# BIRDS-5_FM_-Z_Panel_Ver4.net
KiCad netlist of a schematic drawn in EAGLE
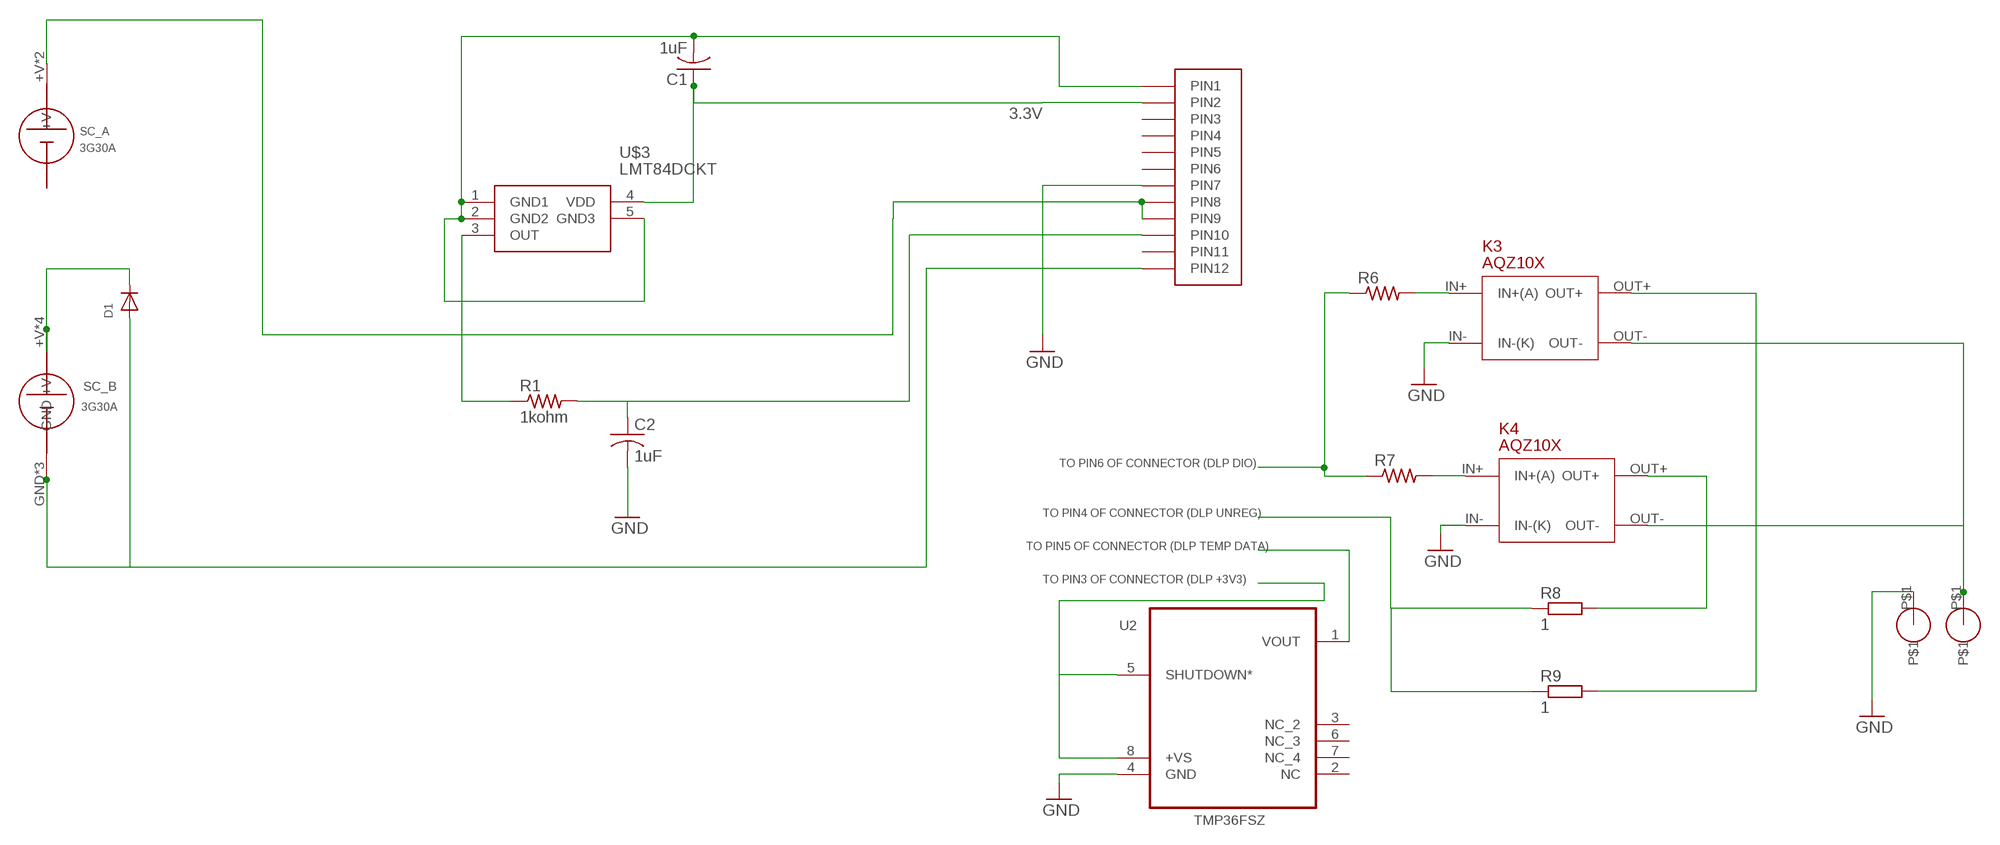
[diagram p0: schematic, sheet 1]

(export (version "E")
  (design (tool "Eeschema 10.0.6"))
  (components
    (comp (ref "C1")
      (value "1uF")
      (footprint "eagle-import:C0805")
      (libsource (lib "eagle-import") (part "C-USC0805"))
    )
    (comp (ref "C2")
      (value "1uF")
      (footprint "eagle-import:C0805")
      (libsource (lib "eagle-import") (part "C-USC0805"))
    )
    (comp (ref "D1")
      (value "DIODE_SOD-123FL")
      (footprint "eagle-import:SOD-123FL")
      (libsource (lib "eagle-import") (part "DIODE_SOD-123FL"))
    )
    (comp (ref "GND9")
      (value "NICR_HOLE")
      (footprint "eagle-import:NICR_HOLE")
      (libsource (lib "eagle-import") (part "NICR_HOLE"))
    )
    (comp (ref "HOLE1")
      (value "NICR_HOLE")
      (footprint "eagle-import:NICR_HOLE")
      (libsource (lib "eagle-import") (part "NICR_HOLE"))
    )
    (comp (ref "K3")
      (value "AQZ10X")
      (footprint "eagle-import:AQZ10X")
      (libsource (lib "eagle-import") (part "AQZ10X"))
    )
    (comp (ref "K4")
      (value "AQZ10X")
      (footprint "eagle-import:AQZ10X")
      (libsource (lib "eagle-import") (part "AQZ10X"))
    )
    (comp (ref "R1")
      (value "1kohm")
      (footprint "eagle-import:R0402")
      (libsource (lib "eagle-import") (part "R-US_R0402"))
    )
    (comp (ref "R6")
      (value "R-US_R0402")
      (footprint "eagle-import:R0402")
      (libsource (lib "eagle-import") (part "adafruit_ufl_R-US_R0402"))
    )
    (comp (ref "R7")
      (value "R-US_R0402")
      (footprint "eagle-import:R0402")
      (libsource (lib "eagle-import") (part "adafruit_ufl_R-US_R0402"))
    )
    (comp (ref "R8")
      (value "1")
      (footprint "eagle-import:R1218")
      (libsource (lib "eagle-import") (part "R-EU_R1218"))
    )
    (comp (ref "R9")
      (value "1")
      (footprint "eagle-import:R1218")
      (libsource (lib "eagle-import") (part "R-EU_R1218"))
    )
    (comp (ref "U$1")
      (value "HEADER12PIN")
      (footprint "eagle-import:HEADER12PIN")
      (libsource (lib "eagle-import") (part "HEADER12PIN"))
    )
    (comp (ref "U$3")
      (value "LMT84DCKT")
      (footprint "eagle-import:SOT65P210X110-5N")
      (fields (field (name "RS_PART_NUMBER") "8115860"))
      (libsource (lib "eagle-import") (part "LMT84DCKT"))
    )
    (comp (ref "U$4")
      (value "SC_A")
      (footprint "eagle-import:SC_A")
      (libsource (lib "eagle-import") (part "SC_A"))
    )
    (comp (ref "U$5")
      (value "SC_B")
      (footprint "eagle-import:SC_B")
      (libsource (lib "eagle-import") (part "SC_B"))
    )
    (comp (ref "U2")
      (value "TMP36FSZ")
      (footprint "eagle-import:SOIC_N")
      (libsource (lib "eagle-import") (part "TMP36FSZ"))
    )
  )
  (nets
    (net (code "1") (name "/3.3V") (class "Default")
      (node (ref "U2") (pin "5") (pinfunction "SHUTDOWN*_5") (pintype "passive"))
      (node (ref "U2") (pin "8") (pinfunction "+VS_8") (pintype "power_in"))
    )
    (net (code "2") (name "GND") (class "Default")
      (node (ref "C1") (pin "2") (pinfunction "2_2") (pintype "passive"))
      (node (ref "C2") (pin "2") (pinfunction "2_2") (pintype "passive"))
      (node (ref "D1") (pin "A") (pinfunction "A_A") (pintype "passive"))
      (node (ref "GND9") (pin "P$1") (pinfunction "P$1_P$1") (pintype "bidirectional"))
      (node (ref "K3") (pin "IN-") (pinfunction "IN-(K)_IN-") (pintype "bidirectional"))
      (node (ref "K4") (pin "IN-") (pinfunction "IN-(K)_IN-") (pintype "bidirectional"))
      (node (ref "U$1") (pin "P1") (pinfunction "PIN1_P1") (pintype "bidirectional"))
      (node (ref "U$1") (pin "P12") (pinfunction "PIN12_P12") (pintype "bidirectional"))
      (node (ref "U$1") (pin "P7") (pinfunction "PIN7_P7") (pintype "bidirectional"))
      (node (ref "U$3") (pin "1") (pinfunction "GND1_1") (pintype "power_in"))
      (node (ref "U$3") (pin "2") (pinfunction "GND2_2") (pintype "power_in"))
      (node (ref "U$3") (pin "5") (pinfunction "GND3_5") (pintype "power_in"))
      (node (ref "U$5") (pin "GND") (pinfunction "GND_GND") (pintype "bidirectional"))
      (node (ref "U$5") (pin "GND1") (pinfunction "GND_GND1") (pintype "bidirectional"))
      (node (ref "U$5") (pin "GND2") (pinfunction "GND_GND2") (pintype "bidirectional"))
      (node (ref "U2") (pin "4") (pinfunction "GND_4") (pintype "passive"))
    )
    (net (code "3") (name "Net-(D1-PadC)") (class "Default")
      (node (ref "D1") (pin "C") (pinfunction "C_C") (pintype "passive"))
      (node (ref "U$5") (pin "+V") (pinfunction "+V_+V") (pintype "bidirectional"))
      (node (ref "U$5") (pin "+V2") (pinfunction "+V_+V2") (pintype "bidirectional"))
      (node (ref "U$5") (pin "+V3") (pinfunction "+V_+V3") (pintype "bidirectional"))
      (node (ref "U$5") (pin "+V4") (pinfunction "+V_+V4") (pintype "bidirectional"))
    )
    (net (code "4") (name "Net-(HOLE1-PadP$1)") (class "Default")
      (node (ref "HOLE1") (pin "P$1") (pinfunction "P$1_P$1") (pintype "bidirectional"))
      (node (ref "K3") (pin "OUT-") (pinfunction "OUT-_OUT-") (pintype "bidirectional"))
      (node (ref "K4") (pin "OUT-") (pinfunction "OUT-_OUT-") (pintype "bidirectional"))
    )
    (net (code "5") (name "Net-(K3-IN+(A))") (class "Default")
      (node (ref "K3") (pin "IN+") (pinfunction "IN+(A)_IN+") (pintype "bidirectional"))
      (node (ref "R6") (pin "2") (pinfunction "2_2") (pintype "passive"))
    )
    (net (code "6") (name "Net-(K3-PadOUT+)") (class "Default")
      (node (ref "K3") (pin "OUT+") (pinfunction "OUT+_OUT+") (pintype "bidirectional"))
      (node (ref "R9") (pin "2") (pinfunction "2_2") (pintype "passive"))
    )
    (net (code "7") (name "Net-(K4-IN+(A))") (class "Default")
      (node (ref "K4") (pin "IN+") (pinfunction "IN+(A)_IN+") (pintype "bidirectional"))
      (node (ref "R7") (pin "2") (pinfunction "2_2") (pintype "passive"))
    )
    (net (code "8") (name "Net-(K4-PadOUT+)") (class "Default")
      (node (ref "K4") (pin "OUT+") (pinfunction "OUT+_OUT+") (pintype "bidirectional"))
      (node (ref "R8") (pin "2") (pinfunction "2_2") (pintype "passive"))
    )
    (net (code "9") (name "Net-(R6-Pad1)") (class "Default")
      (node (ref "R6") (pin "1") (pinfunction "1_1") (pintype "passive"))
      (node (ref "R7") (pin "1") (pinfunction "1_1") (pintype "passive"))
    )
    (net (code "10") (name "Net-(R8-Pad1)") (class "Default")
      (node (ref "R8") (pin "1") (pinfunction "1_1") (pintype "passive"))
      (node (ref "R9") (pin "1") (pinfunction "1_1") (pintype "passive"))
    )
    (net (code "11") (name "Net-(U$1-PIN2)") (class "Default")
      (node (ref "C1") (pin "1") (pinfunction "1_1") (pintype "passive"))
      (node (ref "U$1") (pin "P2") (pinfunction "PIN2_P2") (pintype "bidirectional"))
      (node (ref "U$3") (pin "4") (pinfunction "VDD_4") (pintype "power_in"))
    )
    (net (code "12") (name "Net-(U$1-PIN8)") (class "Default")
      (node (ref "U$1") (pin "P8") (pinfunction "PIN8_P8") (pintype "bidirectional"))
      (node (ref "U$1") (pin "P9") (pinfunction "PIN9_P9") (pintype "bidirectional"))
      (node (ref "U$4") (pin "+V") (pinfunction "+V_+V") (pintype "bidirectional"))
      (node (ref "U$4") (pin "+V1") (pinfunction "+V_+V1") (pintype "bidirectional"))
    )
    (net (code "13") (name "Net-(U$1-PIN10)") (class "Default")
      (node (ref "C2") (pin "1") (pinfunction "1_1") (pintype "passive"))
      (node (ref "R1") (pin "2") (pinfunction "2_2") (pintype "passive"))
      (node (ref "U$1") (pin "P10") (pinfunction "PIN10_P10") (pintype "bidirectional"))
    )
    (net (code "14") (name "Net-(U$3-OUT)") (class "Default")
      (node (ref "R1") (pin "1") (pinfunction "1_1") (pintype "passive"))
      (node (ref "U$3") (pin "3") (pinfunction "OUT_3") (pintype "output"))
    )
    (net (code "15") (name "unconnected-(U$1-PIN3-PadP3)") (class "Default")
      (node (ref "U$1") (pin "P3") (pinfunction "PIN3_P3") (pintype "bidirectional"))
    )
    (net (code "16") (name "unconnected-(U$1-PIN4-PadP4)") (class "Default")
      (node (ref "U$1") (pin "P4") (pinfunction "PIN4_P4") (pintype "bidirectional"))
    )
    (net (code "17") (name "unconnected-(U$1-PIN5-PadP5)") (class "Default")
      (node (ref "U$1") (pin "P5") (pinfunction "PIN5_P5") (pintype "bidirectional"))
    )
    (net (code "18") (name "unconnected-(U$1-PIN6-PadP6)") (class "Default")
      (node (ref "U$1") (pin "P6") (pinfunction "PIN6_P6") (pintype "bidirectional"))
    )
    (net (code "19") (name "unconnected-(U$1-PIN11-PadP11)") (class "Default")
      (node (ref "U$1") (pin "P11") (pinfunction "PIN11_P11") (pintype "bidirectional"))
    )
    (net (code "20") (name "unconnected-(U2-NC-Pad2)") (class "Default")
      (node (ref "U2") (pin "2") (pinfunction "NC_2") (pintype "passive"))
    )
    (net (code "21") (name "unconnected-(U2-NC_2-Pad3)") (class "Default")
      (node (ref "U2") (pin "3") (pinfunction "NC_2_3") (pintype "passive"))
    )
    (net (code "22") (name "unconnected-(U2-NC_3-Pad6)") (class "Default")
      (node (ref "U2") (pin "6") (pinfunction "NC_3_6") (pintype "passive"))
    )
    (net (code "23") (name "unconnected-(U2-NC_4-Pad7)") (class "Default")
      (node (ref "U2") (pin "7") (pinfunction "NC_4_7") (pintype "passive"))
    )
    (net (code "24") (name "unconnected-(U2-VOUT-Pad1)") (class "Default")
      (node (ref "U2") (pin "1") (pinfunction "VOUT_1") (pintype "passive"))
    )
  )
)
